# Miscellaneous.net
KiCad netlist of a schematic drawn in Altium Designer
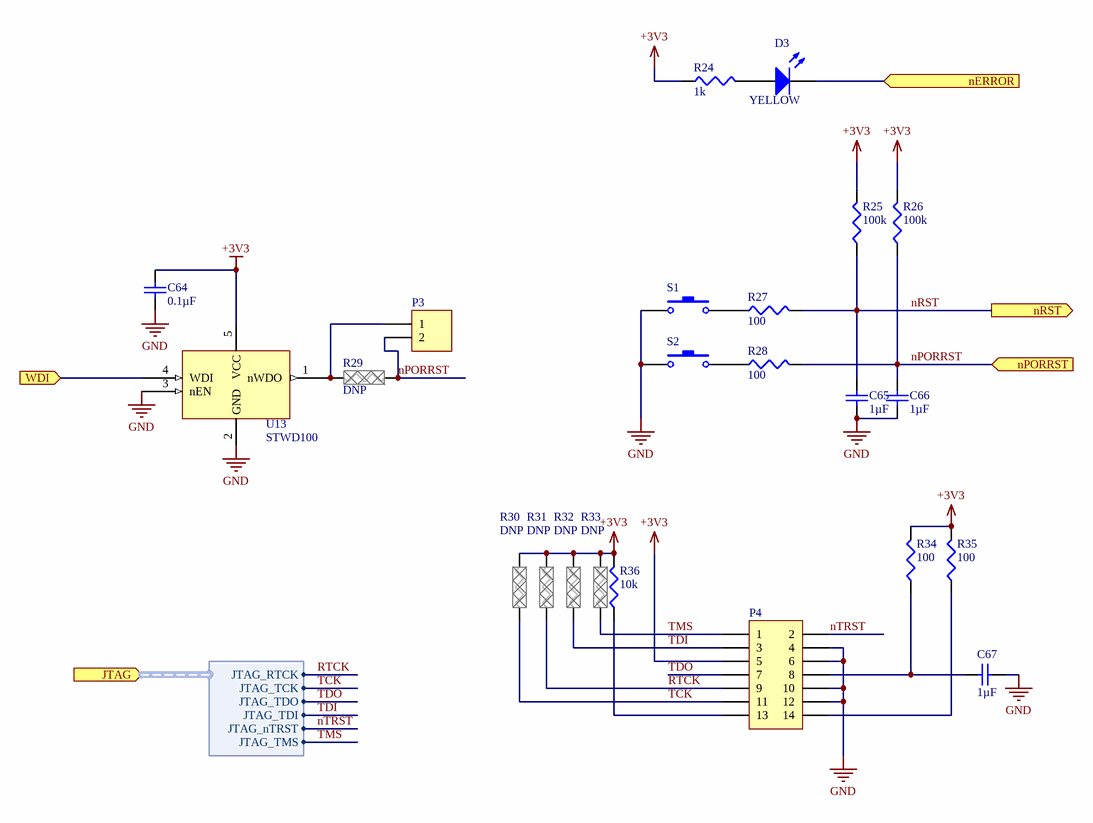
[diagram p0: Miscellaneous.SchDoc]

(export (version "E")
  (design (tool "Eeschema 10.0.6"))
  (components
    (comp (ref "C64")
      (value "0.1µF")
      (footprint "TDK-CGA2B")
      (description "CAP CER 0.1UF 50V X7R 0402")
      (fields
        (field (name "PART NUMBER") "PC-TDK-02259")
        (field (name "MANUFACTURER PART NUMBER") "CGA2B3X7R1H104K050BB")
        (field (name "PUBLISHER") "AlbertaSat")
      )
      (libsource (lib "Database") (part "Cap"))
    )
    (comp (ref "C65")
      (value "1µF")
      (footprint "TDK-CGA3E")
      (description "CAP CER 1UF 16V X5R 0603")
      (fields
        (field (name "PART NUMBER") "PC-TDK-02601")
        (field (name "MANUFACTURER PART NUMBER") "CGA3E1X5R1C105K080AC")
        (field (name "PUBLISHER") "AlbertaSat")
      )
      (libsource (lib "Database") (part "Cap"))
    )
    (comp (ref "C66")
      (value "1µF")
      (footprint "TDK-CGA3E")
      (description "CAP CER 1UF 16V X5R 0603")
      (fields
        (field (name "PART NUMBER") "PC-TDK-02601")
        (field (name "MANUFACTURER PART NUMBER") "CGA3E1X5R1C105K080AC")
        (field (name "PUBLISHER") "AlbertaSat")
      )
      (libsource (lib "Database") (part "Cap"))
    )
    (comp (ref "C67")
      (value "1µF")
      (footprint "TDK-CGA3E")
      (description "CAP CER 1UF 16V X5R 0603")
      (fields
        (field (name "PART NUMBER") "PC-TDK-02601")
        (field (name "MANUFACTURER PART NUMBER") "CGA3E1X5R1C105K080AC")
        (field (name "PUBLISHER") "AlbertaSat")
      )
      (libsource (lib "Database") (part "Cap"))
    )
    (comp (ref "D3")
      (value "YELLOW")
      (footprint "WL-150060XS75000")
      (description "LED YELLOW CLEAR 0603 SMD")
      (fields
        (field (name "PART NUMBER") "5")
        (field (name "MANUFACTURER PART NUMBER") "150060YS75000")
        (field (name "PUBLISHER") "Altium Limited")
      )
      (libsource (lib "Database") (part "LED0"))
    )
    (comp (ref "P3")
      (value "Header 2")
      (footprint "SLN-GRPB021")
      (description "CONN HEADER .050\"\" 3POS PCB GOLD")
      (fields
        (field (name "PART NUMBER") "PP-SLN-00001")
        (field (name "MANUFACTURER PART NUMBER") "GRPB021VWVN-RC")
        (field (name "PUBLISHER") "AlbertaSat")
      )
      (libsource (lib "Database") (part "Header 2"))
    )
    (comp (ref "P4")
      (value "Header 7x2")
      (footprint "HDR2X7")
      (description "CONN HEADER .100\"\" DUAL STR 14POS")
      (fields
        (field (name "PART NUMBER") "PP-SLN-00068")
        (field (name "MANUFACTURER PART NUMBER") "PRPC007DAAN-RC")
        (field (name "PUBLISHER") "AlbertaSat")
      )
      (libsource (lib "Database") (part "Header 7X2"))
    )
    (comp (ref "R24")
      (value "1k")
      (footprint "PANA-ERJ3EK")
      (description "RES SMD 1K OHM 1% 1/10W 0603")
      (fields
        (field (name "PART NUMBER") "15398")
        (field (name "MANUFACTURER PART NUMBER") "ERJ-3EKF1001V")
        (field (name "PUBLISHER") "Altium Limited")
      )
      (libsource (lib "Database") (part "Res3"))
    )
    (comp (ref "R25")
      (value "100k")
      (footprint "PANA-ERJ2R")
      (description "RES SMD 100K OHM 1% 1/10W 0402")
      (fields
        (field (name "PART NUMBER") "18739")
        (field (name "MANUFACTURER PART NUMBER") "ERJ-2RKF1003X")
        (field (name "PUBLISHER") "Altium Limited")
      )
      (libsource (lib "Database") (part "Res3"))
    )
    (comp (ref "R26")
      (value "100k")
      (footprint "PANA-ERJ2R")
      (description "RES SMD 100K OHM 1% 1/10W 0402")
      (fields
        (field (name "PART NUMBER") "18739")
        (field (name "MANUFACTURER PART NUMBER") "ERJ-2RKF1003X")
        (field (name "PUBLISHER") "Altium Limited")
      )
      (libsource (lib "Database") (part "Res3"))
    )
    (comp (ref "R27")
      (value "100")
      (footprint "PANA-ERJ2R")
      (description "RES SMD 100 OHM 1% 1/10W 0402")
      (fields
        (field (name "PART NUMBER") "14081")
        (field (name "MANUFACTURER PART NUMBER") "ERJ-2RKF1000X")
        (field (name "PUBLISHER") "Altium Limited")
      )
      (libsource (lib "Database") (part "Res3"))
    )
    (comp (ref "R28")
      (value "100")
      (footprint "PANA-ERJ2R")
      (description "RES SMD 100 OHM 1% 1/10W 0402")
      (fields
        (field (name "PART NUMBER") "14081")
        (field (name "MANUFACTURER PART NUMBER") "ERJ-2RKF1000X")
        (field (name "PUBLISHER") "Altium Limited")
      )
      (libsource (lib "Database") (part "Res3"))
    )
    (comp (ref "R29")
      (value "DNP")
      (footprint "PANA-ERA2A")
      (fields (field (name "PART NUMBER") "19768"))
      (libsource (lib "Database") (part "DNPRes"))
    )
    (comp (ref "R30")
      (value "DNP")
      (footprint "PANA-ERA2A")
      (fields (field (name "PART NUMBER") "19768"))
      (libsource (lib "Database") (part "DNPRes"))
    )
    (comp (ref "R31")
      (value "DNP")
      (footprint "PANA-ERA2A")
      (fields (field (name "PART NUMBER") "19768"))
      (libsource (lib "Database") (part "DNPRes"))
    )
    (comp (ref "R32")
      (value "DNP")
      (footprint "PANA-ERA2A")
      (fields (field (name "PART NUMBER") "19768"))
      (libsource (lib "Database") (part "DNPRes"))
    )
    (comp (ref "R33")
      (value "DNP")
      (footprint "PANA-ERA2A")
      (fields (field (name "PART NUMBER") "19768"))
      (libsource (lib "Database") (part "DNPRes"))
    )
    (comp (ref "R34")
      (value "100")
      (footprint "PANA-ERJ2R")
      (description "RES SMD 100 OHM 1% 1/10W 0402")
      (fields
        (field (name "PART NUMBER") "14081")
        (field (name "MANUFACTURER PART NUMBER") "ERJ-2RKF1000X")
        (field (name "PUBLISHER") "Altium Limited")
      )
      (libsource (lib "Database") (part "Res3"))
    )
    (comp (ref "R35")
      (value "100")
      (footprint "PANA-ERJ2R")
      (description "RES SMD 100 OHM 1% 1/10W 0402")
      (fields
        (field (name "PART NUMBER") "14081")
        (field (name "MANUFACTURER PART NUMBER") "ERJ-2RKF1000X")
        (field (name "PUBLISHER") "Altium Limited")
      )
      (libsource (lib "Database") (part "Res3"))
    )
    (comp (ref "R36")
      (value "10k")
      (footprint "PANA-ERA2A")
      (description "RES SMD 10K OHM 0.25% 1/16W 0402")
      (fields
        (field (name "PART NUMBER") "17196")
        (field (name "MANUFACTURER PART NUMBER") "ERA-2ARC103X")
        (field (name "PUBLISHER") "Altium Limited")
      )
      (libsource (lib "Database") (part "Res3"))
    )
    (comp (ref "S1")
      (value "1825910-7")
      (footprint "TEC-1825910-7")
      (description "SWITCH TACTILE SPST-NO 0.05A 24V")
      (fields (field (name "PART NUMBER") "452") (field (name "PUBLISHER") "Altium Limited"))
      (libsource (lib "Database") (part "SW-PB"))
    )
    (comp (ref "S2")
      (value "1825910-7")
      (footprint "TEC-1825910-7")
      (description "SWITCH TACTILE SPST-NO 0.05A 24V")
      (fields (field (name "PART NUMBER") "452") (field (name "PUBLISHER") "Altium Limited"))
      (libsource (lib "Database") (part "SW-PB"))
    )
    (comp (ref "U13")
      (value "STWD100")
      (footprint "STM-SOT235")
      (description "IC WATCHDOG TIME CIRCUIT SOT23-5")
      (fields
        (field (name "PART NUMBER") "PU-STM-00004")
        (field (name "MANUFACTURER PART NUMBER") "STWD100YNWWY3F")
        (field (name "PUBLISHER") "AlbertaSat")
      )
      (libsource (lib "Database") (part "STWD100"))
    )
  )
  (nets
    (net (code "2") (name "+3V3") (class "Default")
      (node (ref "C64") (pin "1") (pinfunction "1_1") (pintype "passive"))
      (node (ref "P4") (pin "5") (pinfunction "5_5") (pintype "passive"))
      (node (ref "R24") (pin "1") (pinfunction "1_1") (pintype "passive"))
      (node (ref "R25") (pin "2") (pinfunction "2_2") (pintype "passive"))
      (node (ref "R26") (pin "2") (pinfunction "2_2") (pintype "passive"))
      (node (ref "R30") (pin "2") (pinfunction "2_2") (pintype "passive"))
      (node (ref "R31") (pin "2") (pinfunction "2_2") (pintype "passive"))
      (node (ref "R32") (pin "2") (pinfunction "2_2") (pintype "passive"))
      (node (ref "R33") (pin "2") (pinfunction "2_2") (pintype "passive"))
      (node (ref "R34") (pin "2") (pinfunction "2_2") (pintype "passive"))
      (node (ref "R35") (pin "2") (pinfunction "2_2") (pintype "passive"))
      (node (ref "R36") (pin "2") (pinfunction "2_2") (pintype "passive"))
      (node (ref "U13") (pin "5") (pinfunction "VCC_5") (pintype "passive"))
    )
    (net (code "3") (name "/RTCK") (class "Default")
      (node (ref "P4") (pin "9") (pinfunction "9_9") (pintype "passive"))
      (node (ref "R31") (pin "1") (pinfunction "1_1") (pintype "passive"))
    )
    (net (code "4") (name "/TCK") (class "Default")
      (node (ref "P4") (pin "11") (pinfunction "11_11") (pintype "passive"))
      (node (ref "R30") (pin "1") (pinfunction "1_1") (pintype "passive"))
    )
    (net (code "5") (name "/TDI") (class "Default")
      (node (ref "P4") (pin "3") (pinfunction "3_3") (pintype "passive"))
      (node (ref "R32") (pin "1") (pinfunction "1_1") (pintype "passive"))
    )
    (net (code "6") (name "/TDO") (class "Default")
      (node (ref "P4") (pin "7") (pinfunction "7_7") (pintype "passive"))
    )
    (net (code "7") (name "/TMS") (class "Default")
      (node (ref "P4") (pin "1") (pinfunction "1_1") (pintype "passive"))
      (node (ref "R33") (pin "1") (pinfunction "1_1") (pintype "passive"))
    )
    (net (code "8") (name "/WDI") (class "Default")
      (node (ref "U13") (pin "4") (pinfunction "WDI_4") (pintype "input"))
    )
    (net (code "9") (name "/nERROR") (class "Default")
      (node (ref "D3") (pin "2") (pinfunction "K_2") (pintype "passive"))
    )
    (net (code "10") (name "/nPORRST") (class "Default")
      (node (ref "C66") (pin "2") (pinfunction "2_2") (pintype "passive"))
      (node (ref "P3") (pin "2") (pinfunction "2_2") (pintype "passive"))
      (node (ref "R26") (pin "1") (pinfunction "1_1") (pintype "passive"))
      (node (ref "R28") (pin "2") (pinfunction "2_2") (pintype "passive"))
      (node (ref "R29") (pin "1") (pinfunction "1_1") (pintype "passive"))
    )
    (net (code "11") (name "/nRST") (class "Default")
      (node (ref "C65") (pin "2") (pinfunction "2_2") (pintype "passive"))
      (node (ref "R25") (pin "1") (pinfunction "1_1") (pintype "passive"))
      (node (ref "R27") (pin "2") (pinfunction "2_2") (pintype "passive"))
    )
    (net (code "12") (name "/nTRST") (class "Default")
      (node (ref "P4") (pin "2") (pinfunction "2_2") (pintype "passive"))
    )
    (net (code "14") (name "GND") (class "Default")
      (node (ref "C64") (pin "2") (pinfunction "2_2") (pintype "passive"))
      (node (ref "C65") (pin "1") (pinfunction "1_1") (pintype "passive"))
      (node (ref "C66") (pin "1") (pinfunction "1_1") (pintype "passive"))
      (node (ref "C67") (pin "1") (pinfunction "1_1") (pintype "passive"))
      (node (ref "P4") (pin "10") (pinfunction "10_10") (pintype "passive"))
      (node (ref "P4") (pin "12") (pinfunction "12_12") (pintype "passive"))
      (node (ref "P4") (pin "4") (pinfunction "4_4") (pintype "passive"))
      (node (ref "P4") (pin "6") (pinfunction "6_6") (pintype "passive"))
      (node (ref "S1") (pin "1") (pinfunction "1_1") (pintype "passive"))
      (node (ref "S2") (pin "1") (pinfunction "1_1") (pintype "passive"))
      (node (ref "U13") (pin "2") (pinfunction "GND_2") (pintype "passive"))
      (node (ref "U13") (pin "3") (pinfunction "nEN_3") (pintype "input"))
    )
    (net (code "15") (name "Net-(C67-Pad2)") (class "Default")
      (node (ref "C67") (pin "2") (pinfunction "2_2") (pintype "passive"))
      (node (ref "P4") (pin "8") (pinfunction "8_8") (pintype "passive"))
      (node (ref "R34") (pin "1") (pinfunction "1_1") (pintype "passive"))
    )
    (net (code "16") (name "Net-(D3-A)") (class "Default")
      (node (ref "D3") (pin "1") (pinfunction "A_1") (pintype "passive"))
      (node (ref "R24") (pin "2") (pinfunction "2_2") (pintype "passive"))
    )
    (net (code "17") (name "Net-(P4-Pad13)") (class "Default")
      (node (ref "P4") (pin "13") (pinfunction "13_13") (pintype "passive"))
      (node (ref "R36") (pin "1") (pinfunction "1_1") (pintype "passive"))
    )
    (net (code "18") (name "Net-(P4-Pad14)") (class "Default")
      (node (ref "P4") (pin "14") (pinfunction "14_14") (pintype "passive"))
      (node (ref "R35") (pin "1") (pinfunction "1_1") (pintype "passive"))
    )
    (net (code "19") (name "Net-(R27-Pad1)") (class "Default")
      (node (ref "R27") (pin "1") (pinfunction "1_1") (pintype "passive"))
      (node (ref "S1") (pin "2") (pinfunction "2_2") (pintype "passive"))
    )
    (net (code "20") (name "Net-(R28-Pad1)") (class "Default")
      (node (ref "R28") (pin "1") (pinfunction "1_1") (pintype "passive"))
      (node (ref "S2") (pin "2") (pinfunction "2_2") (pintype "passive"))
    )
    (net (code "21") (name "Net-(U13-nWDO)") (class "Default")
      (node (ref "P3") (pin "1") (pinfunction "1_1") (pintype "passive"))
      (node (ref "R29") (pin "2") (pinfunction "2_2") (pintype "passive"))
      (node (ref "U13") (pin "1") (pinfunction "nWDO_1") (pintype "output"))
    )
  )
)
